# TILE_DEMUX.net
KiCad netlist of a schematic drawn in Altium Designer
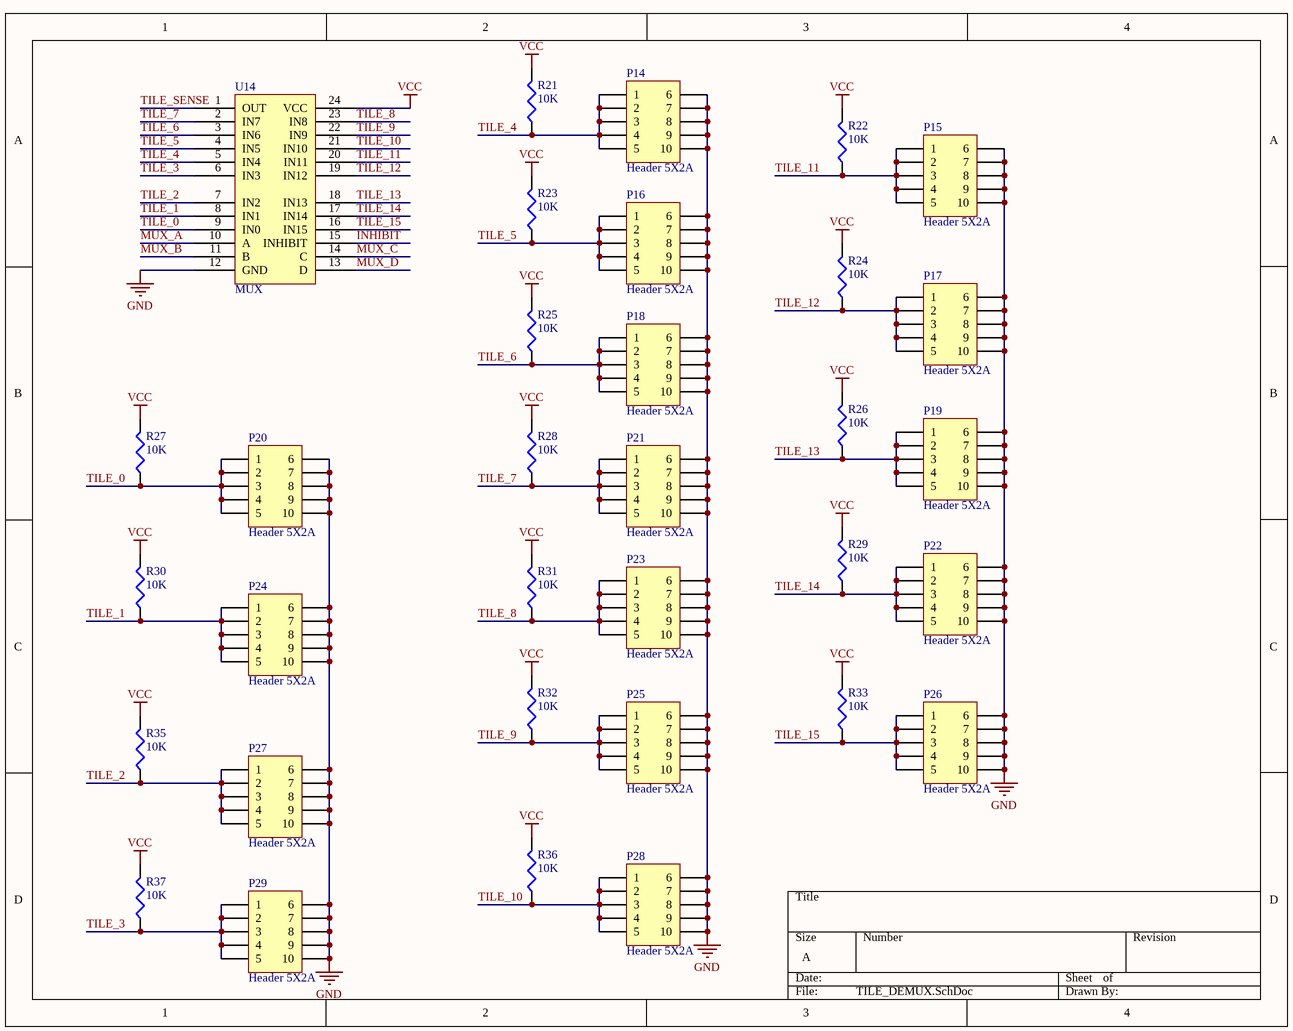
[diagram p0: TILE_DEMUX.SchDoc]

(export (version "E")
  (design (tool "Eeschema 10.0.6"))
  (components
    (comp (ref "P14")
      (value "Header 5X2A")
      (footprint "HDR2X5_CEN")
      (description "Header, 5-Pin, Dual row")
      (fields (field (name "PUBLISHER") "Altium Limited"))
      (libsource (lib "Miscellaneous Connectors") (part "Header 5X2A"))
    )
    (comp (ref "P15")
      (value "Header 5X2A")
      (footprint "HDR2X5_CEN")
      (description "Header, 5-Pin, Dual row")
      (fields (field (name "PUBLISHER") "Altium Limited"))
      (libsource (lib "Miscellaneous Connectors") (part "Header 5X2A"))
    )
    (comp (ref "P16")
      (value "Header 5X2A")
      (footprint "HDR2X5_CEN")
      (description "Header, 5-Pin, Dual row")
      (fields (field (name "PUBLISHER") "Altium Limited"))
      (libsource (lib "Miscellaneous Connectors") (part "Header 5X2A"))
    )
    (comp (ref "P17")
      (value "Header 5X2A")
      (footprint "HDR2X5_CEN")
      (description "Header, 5-Pin, Dual row")
      (fields (field (name "PUBLISHER") "Altium Limited"))
      (libsource (lib "Miscellaneous Connectors") (part "Header 5X2A"))
    )
    (comp (ref "P18")
      (value "Header 5X2A")
      (footprint "HDR2X5_CEN")
      (description "Header, 5-Pin, Dual row")
      (fields (field (name "PUBLISHER") "Altium Limited"))
      (libsource (lib "Miscellaneous Connectors") (part "Header 5X2A"))
    )
    (comp (ref "P19")
      (value "Header 5X2A")
      (footprint "HDR2X5_CEN")
      (description "Header, 5-Pin, Dual row")
      (fields (field (name "PUBLISHER") "Altium Limited"))
      (libsource (lib "Miscellaneous Connectors") (part "Header 5X2A"))
    )
    (comp (ref "P20")
      (value "Header 5X2A")
      (footprint "HDR2X5_CEN")
      (description "Header, 5-Pin, Dual row")
      (fields (field (name "PUBLISHER") "Altium Limited"))
      (libsource (lib "Miscellaneous Connectors") (part "Header 5X2A"))
    )
    (comp (ref "P21")
      (value "Header 5X2A")
      (footprint "HDR2X5_CEN")
      (description "Header, 5-Pin, Dual row")
      (fields (field (name "PUBLISHER") "Altium Limited"))
      (libsource (lib "Miscellaneous Connectors") (part "Header 5X2A"))
    )
    (comp (ref "P22")
      (value "Header 5X2A")
      (footprint "HDR2X5_CEN")
      (description "Header, 5-Pin, Dual row")
      (fields (field (name "PUBLISHER") "Altium Limited"))
      (libsource (lib "Miscellaneous Connectors") (part "Header 5X2A"))
    )
    (comp (ref "P23")
      (value "Header 5X2A")
      (footprint "HDR2X5_CEN")
      (description "Header, 5-Pin, Dual row")
      (fields (field (name "PUBLISHER") "Altium Limited"))
      (libsource (lib "Miscellaneous Connectors") (part "Header 5X2A"))
    )
    (comp (ref "P24")
      (value "Header 5X2A")
      (footprint "HDR2X5_CEN")
      (description "Header, 5-Pin, Dual row")
      (fields (field (name "PUBLISHER") "Altium Limited"))
      (libsource (lib "Miscellaneous Connectors") (part "Header 5X2A"))
    )
    (comp (ref "P25")
      (value "Header 5X2A")
      (footprint "HDR2X5_CEN")
      (description "Header, 5-Pin, Dual row")
      (fields (field (name "PUBLISHER") "Altium Limited"))
      (libsource (lib "Miscellaneous Connectors") (part "Header 5X2A"))
    )
    (comp (ref "P26")
      (value "Header 5X2A")
      (footprint "HDR2X5_CEN")
      (description "Header, 5-Pin, Dual row")
      (fields (field (name "PUBLISHER") "Altium Limited"))
      (libsource (lib "Miscellaneous Connectors") (part "Header 5X2A"))
    )
    (comp (ref "P27")
      (value "Header 5X2A")
      (footprint "HDR2X5_CEN")
      (description "Header, 5-Pin, Dual row")
      (fields (field (name "PUBLISHER") "Altium Limited"))
      (libsource (lib "Miscellaneous Connectors") (part "Header 5X2A"))
    )
    (comp (ref "P28")
      (value "Header 5X2A")
      (footprint "HDR2X5_CEN")
      (description "Header, 5-Pin, Dual row")
      (fields (field (name "PUBLISHER") "Altium Limited"))
      (libsource (lib "Miscellaneous Connectors") (part "Header 5X2A"))
    )
    (comp (ref "P29")
      (value "Header 5X2A")
      (footprint "HDR2X5_CEN")
      (description "Header, 5-Pin, Dual row")
      (fields (field (name "PUBLISHER") "Altium Limited"))
      (libsource (lib "Miscellaneous Connectors") (part "Header 5X2A"))
    )
    (comp (ref "R21")
      (value "10K")
      (footprint "RESC1608L")
      (description "Resistor")
      (fields (field (name "Comment") "Res3") (field (name "PUBLISHER") "Altium Limited"))
      (libsource (lib "Miscellaneous Devices") (part "Res3"))
    )
    (comp (ref "R22")
      (value "10K")
      (footprint "RESC1608L")
      (description "Resistor")
      (fields (field (name "Comment") "Res3") (field (name "PUBLISHER") "Altium Limited"))
      (libsource (lib "Miscellaneous Devices") (part "Res3"))
    )
    (comp (ref "R23")
      (value "10K")
      (footprint "RESC1608L")
      (description "Resistor")
      (fields (field (name "Comment") "Res3") (field (name "PUBLISHER") "Altium Limited"))
      (libsource (lib "Miscellaneous Devices") (part "Res3"))
    )
    (comp (ref "R24")
      (value "10K")
      (footprint "RESC1608L")
      (description "Resistor")
      (fields (field (name "Comment") "Res3") (field (name "PUBLISHER") "Altium Limited"))
      (libsource (lib "Miscellaneous Devices") (part "Res3"))
    )
    (comp (ref "R25")
      (value "10K")
      (footprint "RESC1608L")
      (description "Resistor")
      (fields (field (name "Comment") "Res3") (field (name "PUBLISHER") "Altium Limited"))
      (libsource (lib "Miscellaneous Devices") (part "Res3"))
    )
    (comp (ref "R26")
      (value "10K")
      (footprint "RESC1608L")
      (description "Resistor")
      (fields (field (name "Comment") "Res3") (field (name "PUBLISHER") "Altium Limited"))
      (libsource (lib "Miscellaneous Devices") (part "Res3"))
    )
    (comp (ref "R27")
      (value "10K")
      (footprint "RESC1608L")
      (description "Resistor")
      (fields (field (name "Comment") "Res3") (field (name "PUBLISHER") "Altium Limited"))
      (libsource (lib "Miscellaneous Devices") (part "Res3"))
    )
    (comp (ref "R28")
      (value "10K")
      (footprint "RESC1608L")
      (description "Resistor")
      (fields (field (name "Comment") "Res3") (field (name "PUBLISHER") "Altium Limited"))
      (libsource (lib "Miscellaneous Devices") (part "Res3"))
    )
    (comp (ref "R29")
      (value "10K")
      (footprint "RESC1608L")
      (description "Resistor")
      (fields (field (name "Comment") "Res3") (field (name "PUBLISHER") "Altium Limited"))
      (libsource (lib "Miscellaneous Devices") (part "Res3"))
    )
    (comp (ref "R30")
      (value "10K")
      (footprint "RESC1608L")
      (description "Resistor")
      (fields (field (name "Comment") "Res3") (field (name "PUBLISHER") "Altium Limited"))
      (libsource (lib "Miscellaneous Devices") (part "Res3"))
    )
    (comp (ref "R31")
      (value "10K")
      (footprint "RESC1608L")
      (description "Resistor")
      (fields (field (name "Comment") "Res3") (field (name "PUBLISHER") "Altium Limited"))
      (libsource (lib "Miscellaneous Devices") (part "Res3"))
    )
    (comp (ref "R32")
      (value "10K")
      (footprint "RESC1608L")
      (description "Resistor")
      (fields (field (name "Comment") "Res3") (field (name "PUBLISHER") "Altium Limited"))
      (libsource (lib "Miscellaneous Devices") (part "Res3"))
    )
    (comp (ref "R33")
      (value "10K")
      (footprint "RESC1608L")
      (description "Resistor")
      (fields (field (name "Comment") "Res3") (field (name "PUBLISHER") "Altium Limited"))
      (libsource (lib "Miscellaneous Devices") (part "Res3"))
    )
    (comp (ref "R35")
      (value "10K")
      (footprint "RESC1608L")
      (description "Resistor")
      (fields (field (name "Comment") "Res3") (field (name "PUBLISHER") "Altium Limited"))
      (libsource (lib "Miscellaneous Devices") (part "Res3"))
    )
    (comp (ref "R36")
      (value "10K")
      (footprint "RESC1608L")
      (description "Resistor")
      (fields (field (name "Comment") "Res3") (field (name "PUBLISHER") "Altium Limited"))
      (libsource (lib "Miscellaneous Devices") (part "Res3"))
    )
    (comp (ref "R37")
      (value "10K")
      (footprint "RESC1608L")
      (description "Resistor")
      (fields (field (name "Comment") "Res3") (field (name "PUBLISHER") "Altium Limited"))
      (libsource (lib "Miscellaneous Devices") (part "Res3"))
    )
    (comp (ref "U14") (value "MUX") (footprint "SOIC-24MUX") (libsource (lib "mrone") (part "MUX")))
  )
  (nets
    (net (code "1") (name "/INHIBIT") (class "Default")
      (node (ref "U14") (pin "15") (pinfunction "INHIBIT_15") (pintype "passive"))
    )
    (net (code "2") (name "/MUX_A") (class "Default")
      (node (ref "U14") (pin "10") (pinfunction "A_10") (pintype "passive"))
    )
    (net (code "3") (name "/MUX_B") (class "Default")
      (node (ref "U14") (pin "11") (pinfunction "B_11") (pintype "passive"))
    )
    (net (code "4") (name "/MUX_C") (class "Default")
      (node (ref "U14") (pin "14") (pinfunction "C_14") (pintype "passive"))
    )
    (net (code "5") (name "/MUX_D") (class "Default")
      (node (ref "U14") (pin "13") (pinfunction "D_13") (pintype "passive"))
    )
    (net (code "6") (name "/TILE_0") (class "Default")
      (node (ref "P20") (pin "1") (pinfunction "1_1") (pintype "passive"))
      (node (ref "P20") (pin "2") (pinfunction "2_2") (pintype "passive"))
      (node (ref "P20") (pin "3") (pinfunction "3_3") (pintype "passive"))
      (node (ref "P20") (pin "4") (pinfunction "4_4") (pintype "passive"))
      (node (ref "P20") (pin "5") (pinfunction "5_5") (pintype "passive"))
      (node (ref "R27") (pin "1") (pinfunction "1_1") (pintype "passive"))
      (node (ref "U14") (pin "9") (pinfunction "IN0_9") (pintype "passive"))
    )
    (net (code "7") (name "/TILE_1") (class "Default")
      (node (ref "P24") (pin "1") (pinfunction "1_1") (pintype "passive"))
      (node (ref "P24") (pin "2") (pinfunction "2_2") (pintype "passive"))
      (node (ref "P24") (pin "3") (pinfunction "3_3") (pintype "passive"))
      (node (ref "P24") (pin "4") (pinfunction "4_4") (pintype "passive"))
      (node (ref "P24") (pin "5") (pinfunction "5_5") (pintype "passive"))
      (node (ref "R30") (pin "1") (pinfunction "1_1") (pintype "passive"))
      (node (ref "U14") (pin "8") (pinfunction "IN1_8") (pintype "passive"))
    )
    (net (code "8") (name "/TILE_2") (class "Default")
      (node (ref "P27") (pin "1") (pinfunction "1_1") (pintype "passive"))
      (node (ref "P27") (pin "2") (pinfunction "2_2") (pintype "passive"))
      (node (ref "P27") (pin "3") (pinfunction "3_3") (pintype "passive"))
      (node (ref "P27") (pin "4") (pinfunction "4_4") (pintype "passive"))
      (node (ref "P27") (pin "5") (pinfunction "5_5") (pintype "passive"))
      (node (ref "R35") (pin "1") (pinfunction "1_1") (pintype "passive"))
      (node (ref "U14") (pin "7") (pinfunction "IN2_7") (pintype "passive"))
    )
    (net (code "9") (name "/TILE_3") (class "Default")
      (node (ref "P29") (pin "1") (pinfunction "1_1") (pintype "passive"))
      (node (ref "P29") (pin "2") (pinfunction "2_2") (pintype "passive"))
      (node (ref "P29") (pin "3") (pinfunction "3_3") (pintype "passive"))
      (node (ref "P29") (pin "4") (pinfunction "4_4") (pintype "passive"))
      (node (ref "P29") (pin "5") (pinfunction "5_5") (pintype "passive"))
      (node (ref "R37") (pin "1") (pinfunction "1_1") (pintype "passive"))
      (node (ref "U14") (pin "6") (pinfunction "IN3_6") (pintype "passive"))
    )
    (net (code "10") (name "/TILE_4") (class "Default")
      (node (ref "P14") (pin "1") (pinfunction "1_1") (pintype "passive"))
      (node (ref "P14") (pin "2") (pinfunction "2_2") (pintype "passive"))
      (node (ref "P14") (pin "3") (pinfunction "3_3") (pintype "passive"))
      (node (ref "P14") (pin "4") (pinfunction "4_4") (pintype "passive"))
      (node (ref "P14") (pin "5") (pinfunction "5_5") (pintype "passive"))
      (node (ref "R21") (pin "1") (pinfunction "1_1") (pintype "passive"))
      (node (ref "U14") (pin "5") (pinfunction "IN4_5") (pintype "passive"))
    )
    (net (code "11") (name "/TILE_5") (class "Default")
      (node (ref "P16") (pin "1") (pinfunction "1_1") (pintype "passive"))
      (node (ref "P16") (pin "2") (pinfunction "2_2") (pintype "passive"))
      (node (ref "P16") (pin "3") (pinfunction "3_3") (pintype "passive"))
      (node (ref "P16") (pin "4") (pinfunction "4_4") (pintype "passive"))
      (node (ref "P16") (pin "5") (pinfunction "5_5") (pintype "passive"))
      (node (ref "R23") (pin "1") (pinfunction "1_1") (pintype "passive"))
      (node (ref "U14") (pin "4") (pinfunction "IN5_4") (pintype "passive"))
    )
    (net (code "12") (name "/TILE_6") (class "Default")
      (node (ref "P18") (pin "1") (pinfunction "1_1") (pintype "passive"))
      (node (ref "P18") (pin "2") (pinfunction "2_2") (pintype "passive"))
      (node (ref "P18") (pin "3") (pinfunction "3_3") (pintype "passive"))
      (node (ref "P18") (pin "4") (pinfunction "4_4") (pintype "passive"))
      (node (ref "P18") (pin "5") (pinfunction "5_5") (pintype "passive"))
      (node (ref "R25") (pin "1") (pinfunction "1_1") (pintype "passive"))
      (node (ref "U14") (pin "3") (pinfunction "IN6_3") (pintype "passive"))
    )
    (net (code "13") (name "/TILE_7") (class "Default")
      (node (ref "P21") (pin "1") (pinfunction "1_1") (pintype "passive"))
      (node (ref "P21") (pin "2") (pinfunction "2_2") (pintype "passive"))
      (node (ref "P21") (pin "3") (pinfunction "3_3") (pintype "passive"))
      (node (ref "P21") (pin "4") (pinfunction "4_4") (pintype "passive"))
      (node (ref "P21") (pin "5") (pinfunction "5_5") (pintype "passive"))
      (node (ref "R28") (pin "1") (pinfunction "1_1") (pintype "passive"))
      (node (ref "U14") (pin "2") (pinfunction "IN7_2") (pintype "passive"))
    )
    (net (code "14") (name "/TILE_8") (class "Default")
      (node (ref "P23") (pin "1") (pinfunction "1_1") (pintype "passive"))
      (node (ref "P23") (pin "2") (pinfunction "2_2") (pintype "passive"))
      (node (ref "P23") (pin "3") (pinfunction "3_3") (pintype "passive"))
      (node (ref "P23") (pin "4") (pinfunction "4_4") (pintype "passive"))
      (node (ref "P23") (pin "5") (pinfunction "5_5") (pintype "passive"))
      (node (ref "R31") (pin "1") (pinfunction "1_1") (pintype "passive"))
      (node (ref "U14") (pin "23") (pinfunction "IN8_23") (pintype "passive"))
    )
    (net (code "15") (name "/TILE_9") (class "Default")
      (node (ref "P25") (pin "1") (pinfunction "1_1") (pintype "passive"))
      (node (ref "P25") (pin "2") (pinfunction "2_2") (pintype "passive"))
      (node (ref "P25") (pin "3") (pinfunction "3_3") (pintype "passive"))
      (node (ref "P25") (pin "4") (pinfunction "4_4") (pintype "passive"))
      (node (ref "P25") (pin "5") (pinfunction "5_5") (pintype "passive"))
      (node (ref "R32") (pin "1") (pinfunction "1_1") (pintype "passive"))
      (node (ref "U14") (pin "22") (pinfunction "IN9_22") (pintype "passive"))
    )
    (net (code "16") (name "/TILE_10") (class "Default")
      (node (ref "P28") (pin "1") (pinfunction "1_1") (pintype "passive"))
      (node (ref "P28") (pin "2") (pinfunction "2_2") (pintype "passive"))
      (node (ref "P28") (pin "3") (pinfunction "3_3") (pintype "passive"))
      (node (ref "P28") (pin "4") (pinfunction "4_4") (pintype "passive"))
      (node (ref "P28") (pin "5") (pinfunction "5_5") (pintype "passive"))
      (node (ref "R36") (pin "1") (pinfunction "1_1") (pintype "passive"))
      (node (ref "U14") (pin "21") (pinfunction "IN10_21") (pintype "passive"))
    )
    (net (code "17") (name "/TILE_11") (class "Default")
      (node (ref "P15") (pin "1") (pinfunction "1_1") (pintype "passive"))
      (node (ref "P15") (pin "2") (pinfunction "2_2") (pintype "passive"))
      (node (ref "P15") (pin "3") (pinfunction "3_3") (pintype "passive"))
      (node (ref "P15") (pin "4") (pinfunction "4_4") (pintype "passive"))
      (node (ref "P15") (pin "5") (pinfunction "5_5") (pintype "passive"))
      (node (ref "R22") (pin "1") (pinfunction "1_1") (pintype "passive"))
      (node (ref "U14") (pin "20") (pinfunction "IN11_20") (pintype "passive"))
    )
    (net (code "18") (name "/TILE_12") (class "Default")
      (node (ref "P17") (pin "1") (pinfunction "1_1") (pintype "passive"))
      (node (ref "P17") (pin "2") (pinfunction "2_2") (pintype "passive"))
      (node (ref "P17") (pin "3") (pinfunction "3_3") (pintype "passive"))
      (node (ref "P17") (pin "4") (pinfunction "4_4") (pintype "passive"))
      (node (ref "P17") (pin "5") (pinfunction "5_5") (pintype "passive"))
      (node (ref "R24") (pin "1") (pinfunction "1_1") (pintype "passive"))
      (node (ref "U14") (pin "19") (pinfunction "IN12_19") (pintype "passive"))
    )
    (net (code "19") (name "/TILE_13") (class "Default")
      (node (ref "P19") (pin "1") (pinfunction "1_1") (pintype "passive"))
      (node (ref "P19") (pin "2") (pinfunction "2_2") (pintype "passive"))
      (node (ref "P19") (pin "3") (pinfunction "3_3") (pintype "passive"))
      (node (ref "P19") (pin "4") (pinfunction "4_4") (pintype "passive"))
      (node (ref "P19") (pin "5") (pinfunction "5_5") (pintype "passive"))
      (node (ref "R26") (pin "1") (pinfunction "1_1") (pintype "passive"))
      (node (ref "U14") (pin "18") (pinfunction "IN13_18") (pintype "passive"))
    )
    (net (code "20") (name "/TILE_14") (class "Default")
      (node (ref "P22") (pin "1") (pinfunction "1_1") (pintype "passive"))
      (node (ref "P22") (pin "2") (pinfunction "2_2") (pintype "passive"))
      (node (ref "P22") (pin "3") (pinfunction "3_3") (pintype "passive"))
      (node (ref "P22") (pin "4") (pinfunction "4_4") (pintype "passive"))
      (node (ref "P22") (pin "5") (pinfunction "5_5") (pintype "passive"))
      (node (ref "R29") (pin "1") (pinfunction "1_1") (pintype "passive"))
      (node (ref "U14") (pin "17") (pinfunction "IN14_17") (pintype "passive"))
    )
    (net (code "21") (name "/TILE_15") (class "Default")
      (node (ref "P26") (pin "1") (pinfunction "1_1") (pintype "passive"))
      (node (ref "P26") (pin "2") (pinfunction "2_2") (pintype "passive"))
      (node (ref "P26") (pin "3") (pinfunction "3_3") (pintype "passive"))
      (node (ref "P26") (pin "4") (pinfunction "4_4") (pintype "passive"))
      (node (ref "P26") (pin "5") (pinfunction "5_5") (pintype "passive"))
      (node (ref "R33") (pin "1") (pinfunction "1_1") (pintype "passive"))
      (node (ref "U14") (pin "16") (pinfunction "IN15_16") (pintype "passive"))
    )
    (net (code "22") (name "/TILE_SENSE") (class "Default")
      (node (ref "U14") (pin "1") (pinfunction "OUT_1") (pintype "passive"))
    )
    (net (code "23") (name "GND") (class "Default")
      (node (ref "P14") (pin "10") (pinfunction "10_10") (pintype "passive"))
      (node (ref "P14") (pin "6") (pinfunction "6_6") (pintype "passive"))
      (node (ref "P14") (pin "7") (pinfunction "7_7") (pintype "passive"))
      (node (ref "P14") (pin "8") (pinfunction "8_8") (pintype "passive"))
      (node (ref "P14") (pin "9") (pinfunction "9_9") (pintype "passive"))
      (node (ref "P15") (pin "10") (pinfunction "10_10") (pintype "passive"))
      (node (ref "P15") (pin "6") (pinfunction "6_6") (pintype "passive"))
      (node (ref "P15") (pin "7") (pinfunction "7_7") (pintype "passive"))
      (node (ref "P15") (pin "8") (pinfunction "8_8") (pintype "passive"))
      (node (ref "P15") (pin "9") (pinfunction "9_9") (pintype "passive"))
      (node (ref "P16") (pin "10") (pinfunction "10_10") (pintype "passive"))
      (node (ref "P16") (pin "6") (pinfunction "6_6") (pintype "passive"))
      (node (ref "P16") (pin "7") (pinfunction "7_7") (pintype "passive"))
      (node (ref "P16") (pin "8") (pinfunction "8_8") (pintype "passive"))
      (node (ref "P16") (pin "9") (pinfunction "9_9") (pintype "passive"))
      (node (ref "P17") (pin "10") (pinfunction "10_10") (pintype "passive"))
      (node (ref "P17") (pin "6") (pinfunction "6_6") (pintype "passive"))
      (node (ref "P17") (pin "7") (pinfunction "7_7") (pintype "passive"))
      (node (ref "P17") (pin "8") (pinfunction "8_8") (pintype "passive"))
      (node (ref "P17") (pin "9") (pinfunction "9_9") (pintype "passive"))
      (node (ref "P18") (pin "10") (pinfunction "10_10") (pintype "passive"))
      (node (ref "P18") (pin "6") (pinfunction "6_6") (pintype "passive"))
      (node (ref "P18") (pin "7") (pinfunction "7_7") (pintype "passive"))
      (node (ref "P18") (pin "8") (pinfunction "8_8") (pintype "passive"))
      (node (ref "P18") (pin "9") (pinfunction "9_9") (pintype "passive"))
      (node (ref "P19") (pin "10") (pinfunction "10_10") (pintype "passive"))
      (node (ref "P19") (pin "6") (pinfunction "6_6") (pintype "passive"))
      (node (ref "P19") (pin "7") (pinfunction "7_7") (pintype "passive"))
      (node (ref "P19") (pin "8") (pinfunction "8_8") (pintype "passive"))
      (node (ref "P19") (pin "9") (pinfunction "9_9") (pintype "passive"))
      (node (ref "P20") (pin "10") (pinfunction "10_10") (pintype "passive"))
      (node (ref "P20") (pin "6") (pinfunction "6_6") (pintype "passive"))
      (node (ref "P20") (pin "7") (pinfunction "7_7") (pintype "passive"))
      (node (ref "P20") (pin "8") (pinfunction "8_8") (pintype "passive"))
      (node (ref "P20") (pin "9") (pinfunction "9_9") (pintype "passive"))
      (node (ref "P21") (pin "10") (pinfunction "10_10") (pintype "passive"))
      (node (ref "P21") (pin "6") (pinfunction "6_6") (pintype "passive"))
      (node (ref "P21") (pin "7") (pinfunction "7_7") (pintype "passive"))
      (node (ref "P21") (pin "8") (pinfunction "8_8") (pintype "passive"))
      (node (ref "P21") (pin "9") (pinfunction "9_9") (pintype "passive"))
      (node (ref "P22") (pin "10") (pinfunction "10_10") (pintype "passive"))
      (node (ref "P22") (pin "6") (pinfunction "6_6") (pintype "passive"))
      (node (ref "P22") (pin "7") (pinfunction "7_7") (pintype "passive"))
      (node (ref "P22") (pin "8") (pinfunction "8_8") (pintype "passive"))
      (node (ref "P22") (pin "9") (pinfunction "9_9") (pintype "passive"))
      (node (ref "P23") (pin "10") (pinfunction "10_10") (pintype "passive"))
      (node (ref "P23") (pin "6") (pinfunction "6_6") (pintype "passive"))
      (node (ref "P23") (pin "7") (pinfunction "7_7") (pintype "passive"))
      (node (ref "P23") (pin "8") (pinfunction "8_8") (pintype "passive"))
      (node (ref "P23") (pin "9") (pinfunction "9_9") (pintype "passive"))
      (node (ref "P24") (pin "10") (pinfunction "10_10") (pintype "passive"))
      (node (ref "P24") (pin "6") (pinfunction "6_6") (pintype "passive"))
      (node (ref "P24") (pin "7") (pinfunction "7_7") (pintype "passive"))
      (node (ref "P24") (pin "8") (pinfunction "8_8") (pintype "passive"))
      (node (ref "P24") (pin "9") (pinfunction "9_9") (pintype "passive"))
      (node (ref "P25") (pin "10") (pinfunction "10_10") (pintype "passive"))
      (node (ref "P25") (pin "6") (pinfunction "6_6") (pintype "passive"))
      (node (ref "P25") (pin "7") (pinfunction "7_7") (pintype "passive"))
      (node (ref "P25") (pin "8") (pinfunction "8_8") (pintype "passive"))
      (node (ref "P25") (pin "9") (pinfunction "9_9") (pintype "passive"))
      (node (ref "P26") (pin "10") (pinfunction "10_10") (pintype "passive"))
      (node (ref "P26") (pin "6") (pinfunction "6_6") (pintype "passive"))
      (node (ref "P26") (pin "7") (pinfunction "7_7") (pintype "passive"))
      (node (ref "P26") (pin "8") (pinfunction "8_8") (pintype "passive"))
      (node (ref "P26") (pin "9") (pinfunction "9_9") (pintype "passive"))
      (node (ref "P27") (pin "10") (pinfunction "10_10") (pintype "passive"))
      (node (ref "P27") (pin "6") (pinfunction "6_6") (pintype "passive"))
      (node (ref "P27") (pin "7") (pinfunction "7_7") (pintype "passive"))
      (node (ref "P27") (pin "8") (pinfunction "8_8") (pintype "passive"))
      (node (ref "P27") (pin "9") (pinfunction "9_9") (pintype "passive"))
      (node (ref "P28") (pin "10") (pinfunction "10_10") (pintype "passive"))
      (node (ref "P28") (pin "6") (pinfunction "6_6") (pintype "passive"))
      (node (ref "P28") (pin "7") (pinfunction "7_7") (pintype "passive"))
      (node (ref "P28") (pin "8") (pinfunction "8_8") (pintype "passive"))
      (node (ref "P28") (pin "9") (pinfunction "9_9") (pintype "passive"))
      (node (ref "P29") (pin "10") (pinfunction "10_10") (pintype "passive"))
      (node (ref "P29") (pin "6") (pinfunction "6_6") (pintype "passive"))
      (node (ref "P29") (pin "7") (pinfunction "7_7") (pintype "passive"))
      (node (ref "P29") (pin "8") (pinfunction "8_8") (pintype "passive"))
      (node (ref "P29") (pin "9") (pinfunction "9_9") (pintype "passive"))
      (node (ref "U14") (pin "12") (pinfunction "GND_12") (pintype "passive"))
    )
    (net (code "24") (name "VCC") (class "Default")
      (node (ref "R21") (pin "2") (pinfunction "2_2") (pintype "passive"))
      (node (ref "R22") (pin "2") (pinfunction "2_2") (pintype "passive"))
      (node (ref "R23") (pin "2") (pinfunction "2_2") (pintype "passive"))
      (node (ref "R24") (pin "2") (pinfunction "2_2") (pintype "passive"))
      (node (ref "R25") (pin "2") (pinfunction "2_2") (pintype "passive"))
      (node (ref "R26") (pin "2") (pinfunction "2_2") (pintype "passive"))
      (node (ref "R27") (pin "2") (pinfunction "2_2") (pintype "passive"))
      (node (ref "R28") (pin "2") (pinfunction "2_2") (pintype "passive"))
      (node (ref "R29") (pin "2") (pinfunction "2_2") (pintype "passive"))
      (node (ref "R30") (pin "2") (pinfunction "2_2") (pintype "passive"))
      (node (ref "R31") (pin "2") (pinfunction "2_2") (pintype "passive"))
      (node (ref "R32") (pin "2") (pinfunction "2_2") (pintype "passive"))
      (node (ref "R33") (pin "2") (pinfunction "2_2") (pintype "passive"))
      (node (ref "R35") (pin "2") (pinfunction "2_2") (pintype "passive"))
      (node (ref "R36") (pin "2") (pinfunction "2_2") (pintype "passive"))
      (node (ref "R37") (pin "2") (pinfunction "2_2") (pintype "passive"))
      (node (ref "U14") (pin "24") (pinfunction "VCC_24") (pintype "passive"))
    )
  )
)
